# MSSRP-RTC.net
KiCad netlist of a schematic drawn in EAGLE
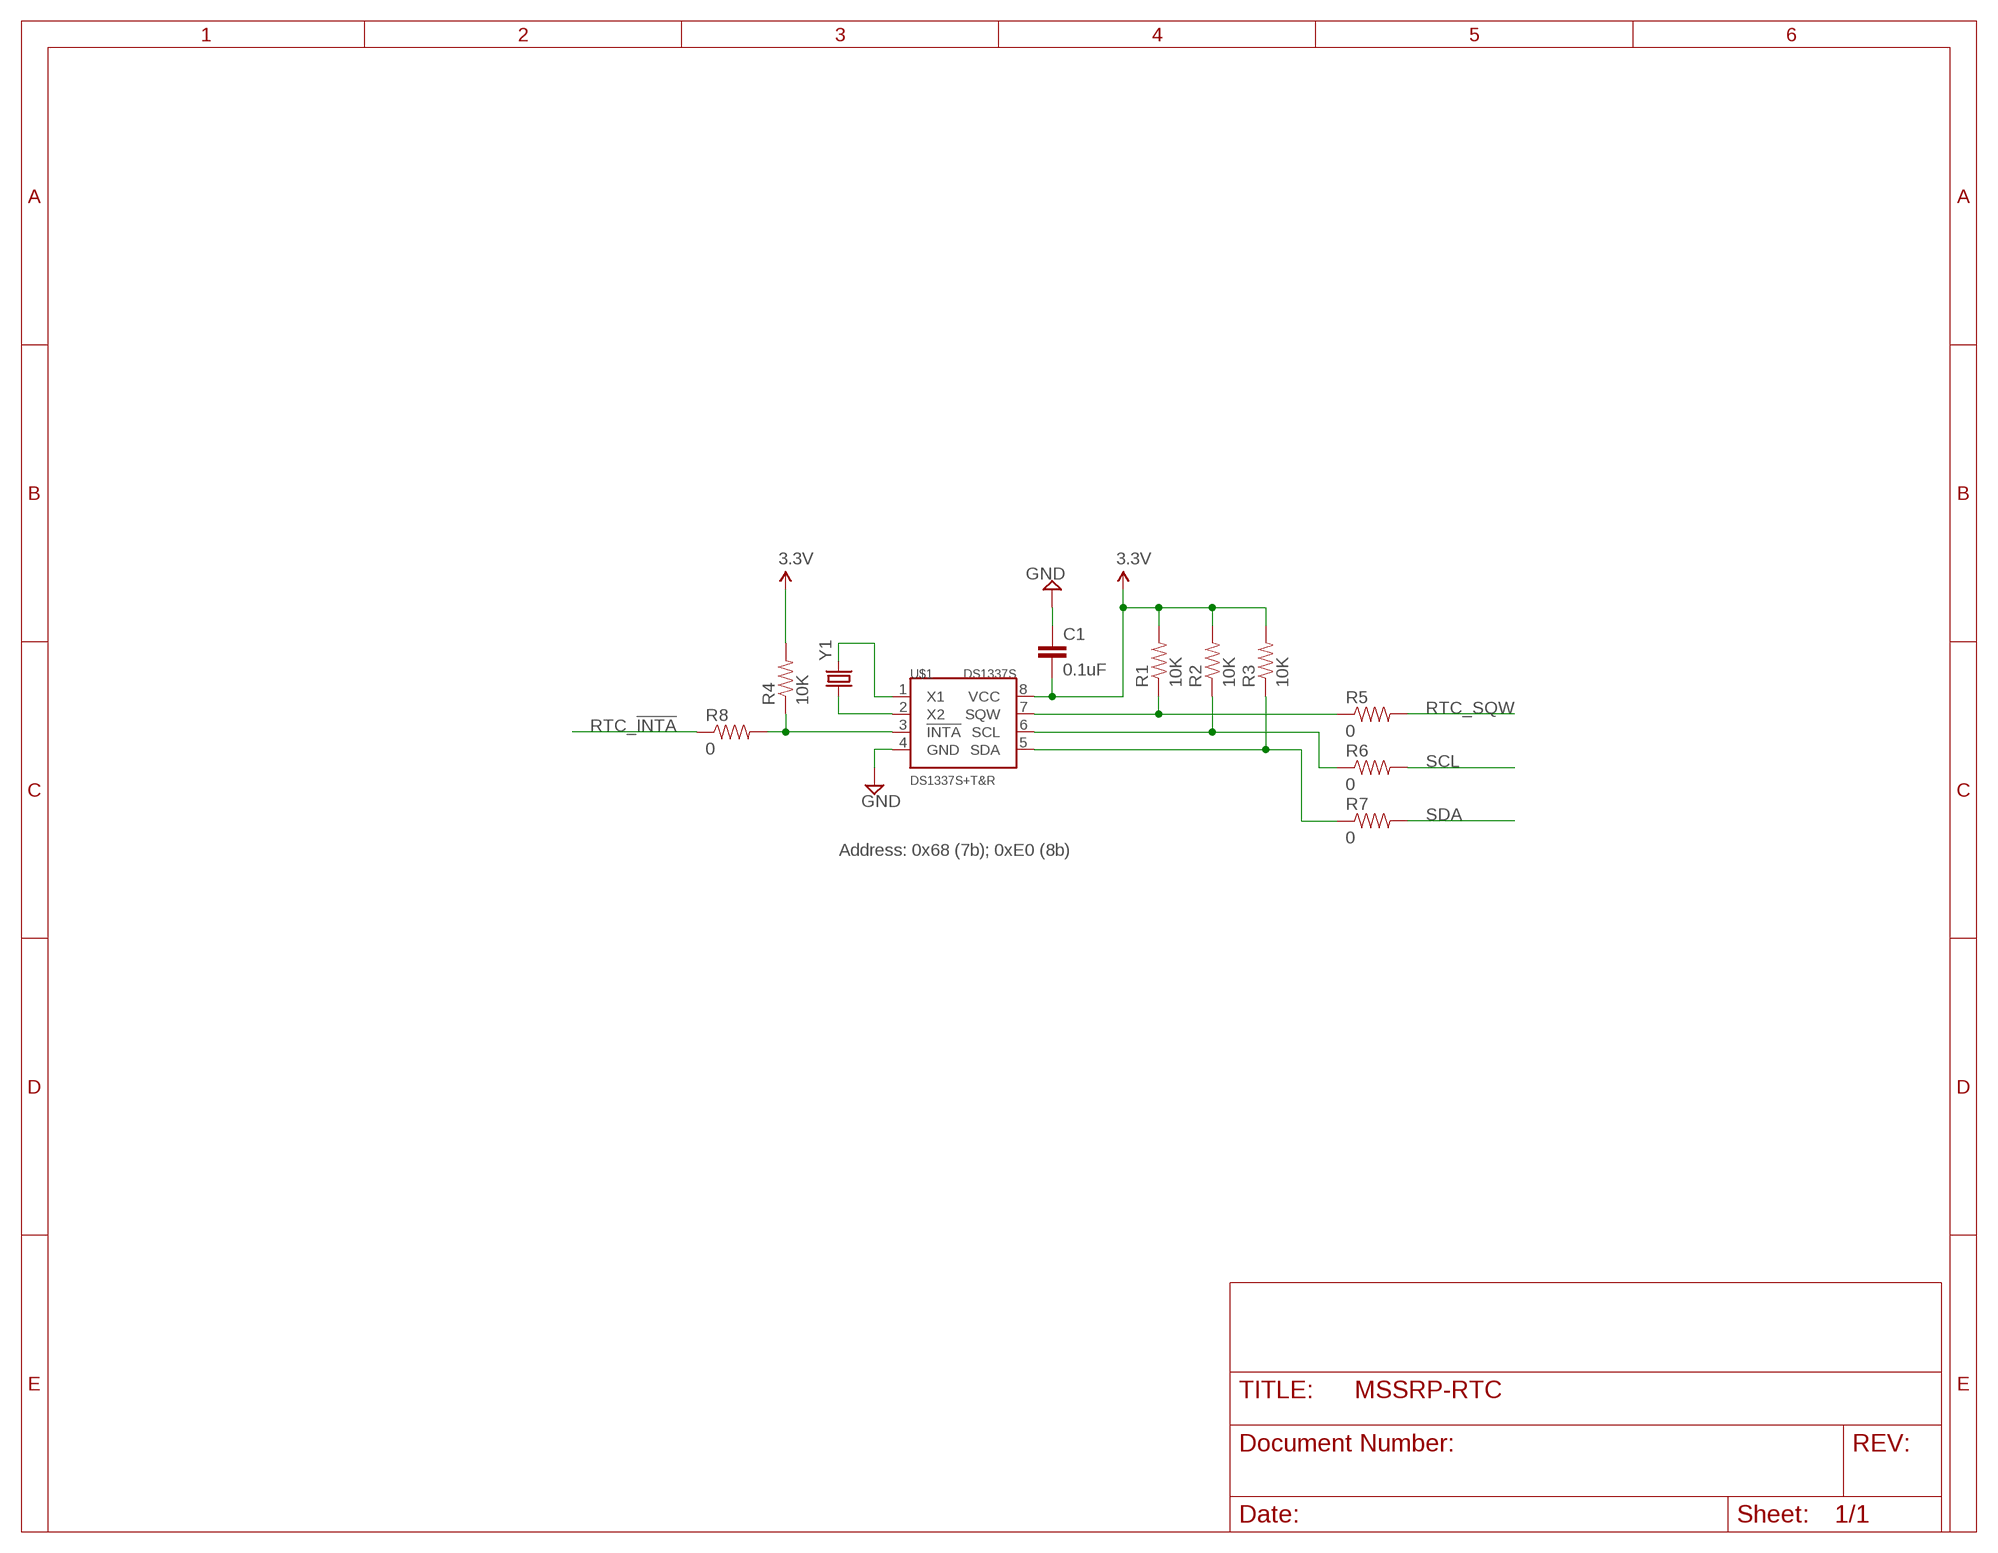
[diagram p0: schematic, sheet 1]

(export (version "E")
  (design (tool "Eeschema 10.0.6"))
  (components
    (comp (ref "C1")
      (value "0.1uF")
      (footprint "eagle-import:0603-CAP")
      (libsource (lib "eagle-import") (part "0.1UF-25V-5%(0603)"))
    )
    (comp (ref "R1")
      (value "10K")
      (footprint "eagle-import:0603-RES")
      (libsource (lib "eagle-import") (part "10KOHM1/10W1%(0603)0603"))
    )
    (comp (ref "R2")
      (value "10K")
      (footprint "eagle-import:0603-RES")
      (libsource (lib "eagle-import") (part "10KOHM1/10W1%(0603)0603"))
    )
    (comp (ref "R3")
      (value "10K")
      (footprint "eagle-import:0603-RES")
      (libsource (lib "eagle-import") (part "10KOHM1/10W1%(0603)0603"))
    )
    (comp (ref "R4")
      (value "10K")
      (footprint "eagle-import:0603-RES")
      (libsource (lib "eagle-import") (part "10KOHM1/10W1%(0603)0603"))
    )
    (comp (ref "R5")
      (value "0")
      (footprint "eagle-import:0603")
      (libsource (lib "eagle-import") (part "0OHM1/10W5%(0603)"))
    )
    (comp (ref "R6")
      (value "0")
      (footprint "eagle-import:0603")
      (libsource (lib "eagle-import") (part "0OHM1/10W5%(0603)"))
    )
    (comp (ref "R7")
      (value "0")
      (footprint "eagle-import:0603")
      (libsource (lib "eagle-import") (part "0OHM1/10W5%(0603)"))
    )
    (comp (ref "R8")
      (value "0")
      (footprint "eagle-import:0603")
      (libsource (lib "eagle-import") (part "0OHM1/10W5%(0603)"))
    )
    (comp (ref "U$1")
      (value "DS1337S+T&R")
      (footprint "eagle-import:SOIC8")
      (libsource (lib "eagle-import") (part "DS1337S+T&R"))
    )
    (comp (ref "Y1")
      (value "CRYSTALSMD")
      (footprint "eagle-import:HC49UP")
      (libsource (lib "eagle-import") (part "CRYSTALSMD"))
    )
  )
  (nets
    (net (code "1") (name "/RTC_SQW") (class "Default")
      (node (ref "R5") (pin "2") (pinfunction "2_2") (pintype "passive"))
    )
    (net (code "2") (name "/RTC_~{INTA}") (class "Default")
      (node (ref "R8") (pin "1") (pinfunction "1_1") (pintype "passive"))
    )
    (net (code "3") (name "/SCL") (class "Default")
      (node (ref "R6") (pin "2") (pinfunction "2_2") (pintype "passive"))
    )
    (net (code "4") (name "/SDA") (class "Default")
      (node (ref "R7") (pin "2") (pinfunction "2_2") (pintype "passive"))
    )
    (net (code "5") (name "3.3V") (class "Default")
      (node (ref "C1") (pin "2") (pinfunction "2_2") (pintype "passive"))
      (node (ref "R1") (pin "2") (pinfunction "2_2") (pintype "passive"))
      (node (ref "R2") (pin "2") (pinfunction "2_2") (pintype "passive"))
      (node (ref "R3") (pin "2") (pinfunction "2_2") (pintype "passive"))
      (node (ref "R4") (pin "2") (pinfunction "2_2") (pintype "passive"))
      (node (ref "U$1") (pin "8") (pinfunction "VCC_8") (pintype "power_in"))
    )
    (net (code "6") (name "GND") (class "Default")
      (node (ref "C1") (pin "1") (pinfunction "1_1") (pintype "passive"))
      (node (ref "U$1") (pin "4") (pinfunction "GND_4") (pintype "power_in"))
    )
    (net (code "7") (name "Net-(U$1-SCL)") (class "Default")
      (node (ref "R2") (pin "1") (pinfunction "1_1") (pintype "passive"))
      (node (ref "R6") (pin "1") (pinfunction "1_1") (pintype "passive"))
      (node (ref "U$1") (pin "6") (pinfunction "SCL_6") (pintype "bidirectional"))
    )
    (net (code "8") (name "Net-(U$1-SDA)") (class "Default")
      (node (ref "R3") (pin "1") (pinfunction "1_1") (pintype "passive"))
      (node (ref "R7") (pin "1") (pinfunction "1_1") (pintype "passive"))
      (node (ref "U$1") (pin "5") (pinfunction "SDA_5") (pintype "bidirectional"))
    )
    (net (code "9") (name "Net-(U$1-SQW)") (class "Default")
      (node (ref "R1") (pin "1") (pinfunction "1_1") (pintype "passive"))
      (node (ref "R5") (pin "1") (pinfunction "1_1") (pintype "passive"))
      (node (ref "U$1") (pin "7") (pinfunction "SQW_7") (pintype "bidirectional"))
    )
    (net (code "10") (name "Net-(U$1-X1)") (class "Default")
      (node (ref "U$1") (pin "1") (pinfunction "X1_1") (pintype "passive"))
      (node (ref "Y1") (pin "2") (pinfunction "2_2") (pintype "passive"))
    )
    (net (code "11") (name "Net-(U$1-X2)") (class "Default")
      (node (ref "U$1") (pin "2") (pinfunction "X2_2") (pintype "passive"))
      (node (ref "Y1") (pin "1") (pinfunction "1_1") (pintype "passive"))
    )
    (net (code "12") (name "Net-(U$1-~{INTA})") (class "Default")
      (node (ref "R4") (pin "1") (pinfunction "1_1") (pintype "passive"))
      (node (ref "R8") (pin "2") (pinfunction "2_2") (pintype "passive"))
      (node (ref "U$1") (pin "3") (pinfunction "~{INTA}_3") (pintype "bidirectional"))
    )
  )
)
